# Circuit_version_4.net
KiCad netlist of a schematic drawn in Altium Designer
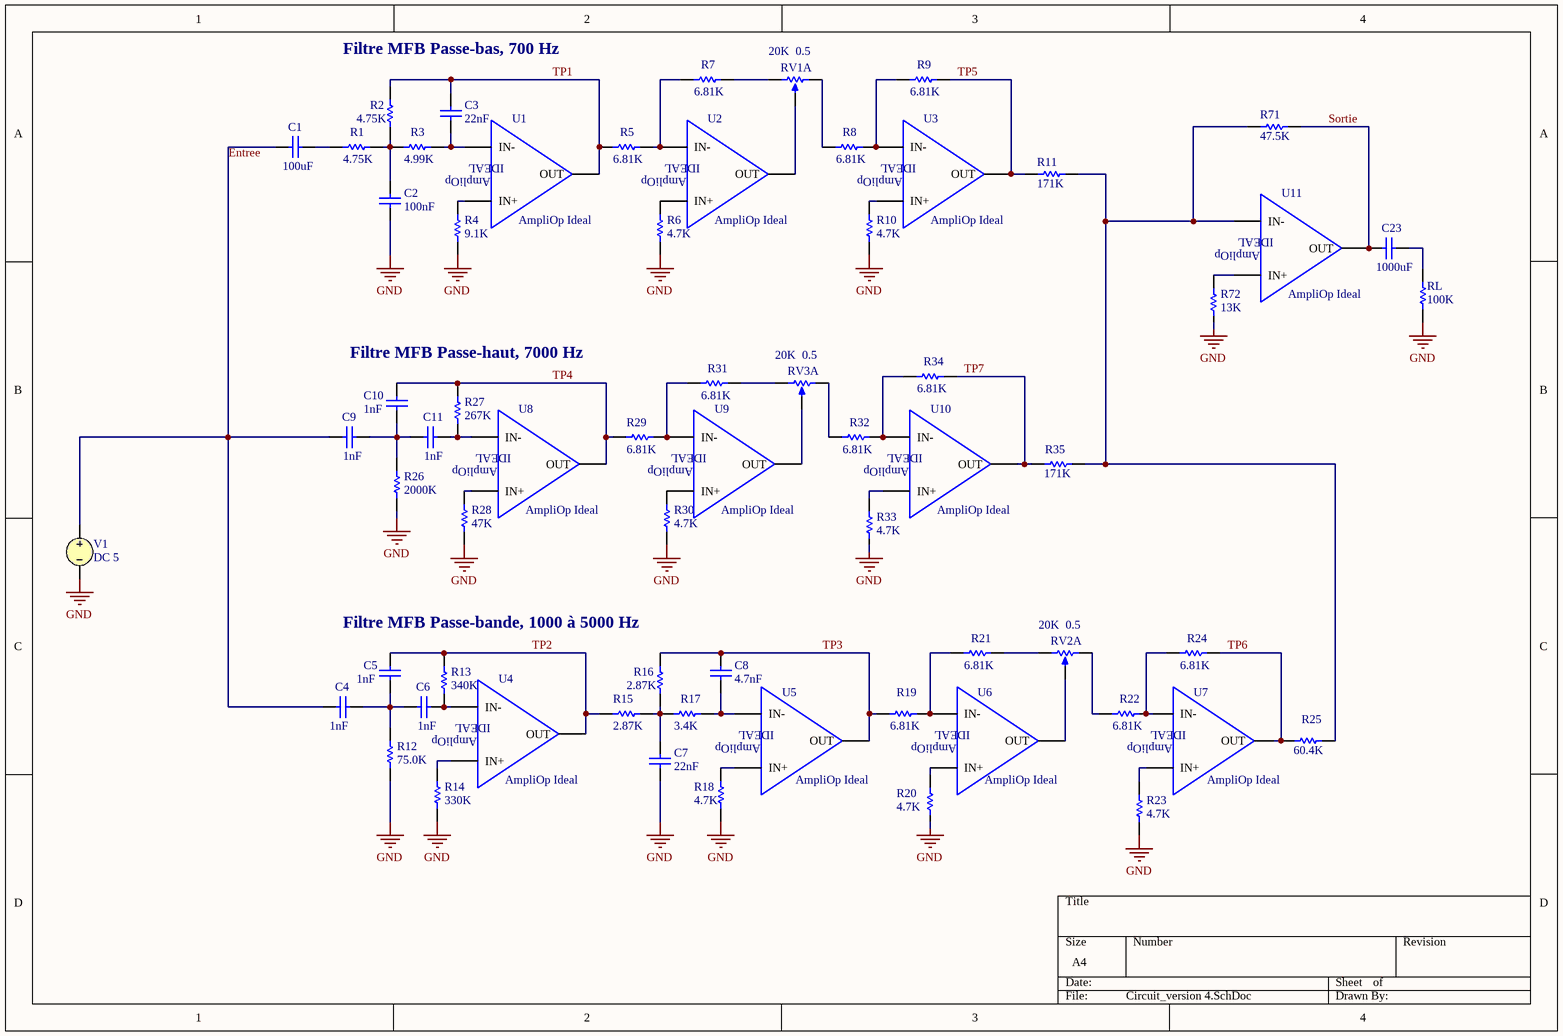
[diagram p0: Circuit_version 4.SchDoc]

(export (version "E")
  (design (tool "Eeschema 10.0.6"))
  (components
    (comp (ref "C1")
      (value "100uF")
      (footprint "RAD-0.3")
      (description "Capacitor")
      (fields (field (name "Comment") "Cap") (field (name "PUBLISHER") "Altium Limited"))
      (libsource (lib "Miscellaneous Devices") (part "Cap"))
    )
    (comp (ref "C2")
      (value "100nF")
      (footprint "RAD-0.3")
      (description "Capacitor")
      (fields (field (name "Comment") "Cap") (field (name "PUBLISHER") "Altium Limited"))
      (libsource (lib "Miscellaneous Devices") (part "Cap"))
    )
    (comp (ref "C3")
      (value "22nF")
      (footprint "RAD-0.3")
      (description "Capacitor")
      (fields (field (name "Comment") "Cap") (field (name "PUBLISHER") "Altium Limited"))
      (libsource (lib "Miscellaneous Devices") (part "Cap"))
    )
    (comp (ref "C4")
      (value "1nF")
      (footprint "RAD-0.3")
      (description "Capacitor")
      (fields (field (name "Comment") "Cap") (field (name "PUBLISHER") "Altium Limited"))
      (libsource (lib "Miscellaneous Devices") (part "Cap"))
    )
    (comp (ref "C5")
      (value "1nF")
      (footprint "RAD-0.3")
      (description "Capacitor")
      (fields (field (name "Comment") "Cap") (field (name "PUBLISHER") "Altium Limited"))
      (libsource (lib "Miscellaneous Devices") (part "Cap"))
    )
    (comp (ref "C6")
      (value "1nF")
      (footprint "RAD-0.3")
      (description "Capacitor")
      (fields (field (name "Comment") "Cap") (field (name "PUBLISHER") "Altium Limited"))
      (libsource (lib "Miscellaneous Devices") (part "Cap"))
    )
    (comp (ref "C7")
      (value "22nF")
      (footprint "RAD-0.3")
      (description "Capacitor")
      (fields (field (name "Comment") "Cap") (field (name "PUBLISHER") "Altium Limited"))
      (libsource (lib "Miscellaneous Devices") (part "Cap"))
    )
    (comp (ref "C8")
      (value "4.7nF")
      (footprint "RAD-0.3")
      (description "Capacitor")
      (fields (field (name "Comment") "Cap") (field (name "PUBLISHER") "Altium Limited"))
      (libsource (lib "Miscellaneous Devices") (part "Cap"))
    )
    (comp (ref "C9")
      (value "1nF")
      (footprint "RAD-0.3")
      (description "Capacitor")
      (fields (field (name "Comment") "Cap") (field (name "PUBLISHER") "Altium Limited"))
      (libsource (lib "Miscellaneous Devices") (part "Cap"))
    )
    (comp (ref "C10")
      (value "1nF")
      (footprint "RAD-0.3")
      (description "Capacitor")
      (fields (field (name "Comment") "Cap") (field (name "PUBLISHER") "Altium Limited"))
      (libsource (lib "Miscellaneous Devices") (part "Cap"))
    )
    (comp (ref "C11")
      (value "1nF")
      (footprint "RAD-0.3")
      (description "Capacitor")
      (fields (field (name "Comment") "Cap") (field (name "PUBLISHER") "Altium Limited"))
      (libsource (lib "Miscellaneous Devices") (part "Cap"))
    )
    (comp (ref "C23")
      (value "1000uF")
      (footprint "RAD-0.3")
      (description "Capacitor")
      (fields (field (name "Comment") "Cap") (field (name "PUBLISHER") "Altium Limited"))
      (libsource (lib "Miscellaneous Devices") (part "Cap"))
    )
    (comp (ref "R1")
      (value "4.75K")
      (footprint "AXIAL-0.3")
      (description "Resistor")
      (fields (field (name "Comment") "Res1") (field (name "PUBLISHER") "Altium Limited"))
      (libsource (lib "Miscellaneous Devices") (part "Res1"))
    )
    (comp (ref "R2")
      (value "4.75K")
      (footprint "AXIAL-0.3")
      (description "Resistor")
      (fields (field (name "Comment") "Res1") (field (name "PUBLISHER") "Altium Limited"))
      (libsource (lib "Miscellaneous Devices") (part "Res1"))
    )
    (comp (ref "R3")
      (value "4.99K")
      (footprint "AXIAL-0.3")
      (description "Resistor")
      (fields (field (name "Comment") "Res1") (field (name "PUBLISHER") "Altium Limited"))
      (libsource (lib "Miscellaneous Devices") (part "Res1"))
    )
    (comp (ref "R4")
      (value "9.1K")
      (footprint "AXIAL-0.3")
      (description "Resistor")
      (fields (field (name "Comment") "Res1") (field (name "PUBLISHER") "Altium Limited"))
      (libsource (lib "Miscellaneous Devices") (part "Res1"))
    )
    (comp (ref "R5")
      (value "6.81K")
      (footprint "AXIAL-0.3")
      (description "Resistor")
      (fields (field (name "Comment") "Res1") (field (name "PUBLISHER") "Altium Limited"))
      (libsource (lib "Miscellaneous Devices") (part "Res1"))
    )
    (comp (ref "R6")
      (value "4.7K")
      (footprint "AXIAL-0.3")
      (description "Resistor")
      (fields (field (name "Comment") "Res1") (field (name "PUBLISHER") "Altium Limited"))
      (libsource (lib "Miscellaneous Devices") (part "Res1"))
    )
    (comp (ref "R7")
      (value "6.81K")
      (footprint "AXIAL-0.3")
      (description "Resistor")
      (fields (field (name "Comment") "Res1") (field (name "PUBLISHER") "Altium Limited"))
      (libsource (lib "Miscellaneous Devices") (part "Res1"))
    )
    (comp (ref "R8")
      (value "6.81K")
      (footprint "AXIAL-0.3")
      (description "Resistor")
      (fields (field (name "Comment") "Res1") (field (name "PUBLISHER") "Altium Limited"))
      (libsource (lib "Miscellaneous Devices") (part "Res1"))
    )
    (comp (ref "R9")
      (value "6.81K")
      (footprint "AXIAL-0.3")
      (description "Resistor")
      (fields (field (name "Comment") "Res1") (field (name "PUBLISHER") "Altium Limited"))
      (libsource (lib "Miscellaneous Devices") (part "Res1"))
    )
    (comp (ref "R10")
      (value "4.7K")
      (footprint "AXIAL-0.3")
      (description "Resistor")
      (fields (field (name "Comment") "Res1") (field (name "PUBLISHER") "Altium Limited"))
      (libsource (lib "Miscellaneous Devices") (part "Res1"))
    )
    (comp (ref "R11")
      (value "171K")
      (footprint "AXIAL-0.3")
      (description "Resistor")
      (fields (field (name "Comment") "Res1") (field (name "PUBLISHER") "Altium Limited"))
      (libsource (lib "Miscellaneous Devices") (part "Res1"))
    )
    (comp (ref "R12")
      (value "75.0K")
      (footprint "AXIAL-0.3")
      (description "Resistor")
      (fields (field (name "Comment") "Res1") (field (name "PUBLISHER") "Altium Limited"))
      (libsource (lib "Miscellaneous Devices") (part "Res1"))
    )
    (comp (ref "R13")
      (value "340K")
      (footprint "AXIAL-0.3")
      (description "Resistor")
      (fields (field (name "Comment") "Res1") (field (name "PUBLISHER") "Altium Limited"))
      (libsource (lib "Miscellaneous Devices") (part "Res1"))
    )
    (comp (ref "R14")
      (value "330K")
      (footprint "AXIAL-0.3")
      (description "Resistor")
      (fields (field (name "Comment") "Res1") (field (name "PUBLISHER") "Altium Limited"))
      (libsource (lib "Miscellaneous Devices") (part "Res1"))
    )
    (comp (ref "R15")
      (value "2.87K")
      (footprint "AXIAL-0.3")
      (description "Resistor")
      (fields (field (name "Comment") "Res1") (field (name "PUBLISHER") "Altium Limited"))
      (libsource (lib "Miscellaneous Devices") (part "Res1"))
    )
    (comp (ref "R16")
      (value "2.87K")
      (footprint "AXIAL-0.3")
      (description "Resistor")
      (fields (field (name "Comment") "Res1") (field (name "PUBLISHER") "Altium Limited"))
      (libsource (lib "Miscellaneous Devices") (part "Res1"))
    )
    (comp (ref "R17")
      (value "3.4K")
      (footprint "AXIAL-0.3")
      (description "Resistor")
      (fields (field (name "Comment") "Res1") (field (name "PUBLISHER") "Altium Limited"))
      (libsource (lib "Miscellaneous Devices") (part "Res1"))
    )
    (comp (ref "R18")
      (value "4.7K")
      (footprint "AXIAL-0.3")
      (description "Resistor")
      (fields (field (name "Comment") "Res1") (field (name "PUBLISHER") "Altium Limited"))
      (libsource (lib "Miscellaneous Devices") (part "Res1"))
    )
    (comp (ref "R19")
      (value "6.81K")
      (footprint "AXIAL-0.3")
      (description "Resistor")
      (fields (field (name "Comment") "Res1") (field (name "PUBLISHER") "Altium Limited"))
      (libsource (lib "Miscellaneous Devices") (part "Res1"))
    )
    (comp (ref "R20")
      (value "4.7K")
      (footprint "AXIAL-0.3")
      (description "Resistor")
      (fields (field (name "Comment") "Res1") (field (name "PUBLISHER") "Altium Limited"))
      (libsource (lib "Miscellaneous Devices") (part "Res1"))
    )
    (comp (ref "R21")
      (value "6.81K")
      (footprint "AXIAL-0.3")
      (description "Resistor")
      (fields (field (name "Comment") "Res1") (field (name "PUBLISHER") "Altium Limited"))
      (libsource (lib "Miscellaneous Devices") (part "Res1"))
    )
    (comp (ref "R22")
      (value "6.81K")
      (footprint "AXIAL-0.3")
      (description "Resistor")
      (fields (field (name "Comment") "Res1") (field (name "PUBLISHER") "Altium Limited"))
      (libsource (lib "Miscellaneous Devices") (part "Res1"))
    )
    (comp (ref "R23")
      (value "4.7K")
      (footprint "AXIAL-0.3")
      (description "Resistor")
      (fields (field (name "Comment") "Res1") (field (name "PUBLISHER") "Altium Limited"))
      (libsource (lib "Miscellaneous Devices") (part "Res1"))
    )
    (comp (ref "R24")
      (value "6.81K")
      (footprint "AXIAL-0.3")
      (description "Resistor")
      (fields (field (name "Comment") "Res1") (field (name "PUBLISHER") "Altium Limited"))
      (libsource (lib "Miscellaneous Devices") (part "Res1"))
    )
    (comp (ref "R25")
      (value "60.4K")
      (footprint "AXIAL-0.3")
      (description "Resistor")
      (fields (field (name "Comment") "Res1") (field (name "PUBLISHER") "Altium Limited"))
      (libsource (lib "Miscellaneous Devices") (part "Res1"))
    )
    (comp (ref "R26")
      (value "2000K")
      (footprint "AXIAL-0.3")
      (description "Resistor")
      (fields (field (name "Comment") "Res1") (field (name "PUBLISHER") "Altium Limited"))
      (libsource (lib "Miscellaneous Devices") (part "Res1"))
    )
    (comp (ref "R27")
      (value "267K")
      (footprint "AXIAL-0.3")
      (description "Resistor")
      (fields (field (name "Comment") "Res1") (field (name "PUBLISHER") "Altium Limited"))
      (libsource (lib "Miscellaneous Devices") (part "Res1"))
    )
    (comp (ref "R28")
      (value "47K")
      (footprint "AXIAL-0.3")
      (description "Resistor")
      (fields (field (name "Comment") "Res1") (field (name "PUBLISHER") "Altium Limited"))
      (libsource (lib "Miscellaneous Devices") (part "Res1"))
    )
    (comp (ref "R29")
      (value "6.81K")
      (footprint "AXIAL-0.3")
      (description "Resistor")
      (fields (field (name "Comment") "Res1") (field (name "PUBLISHER") "Altium Limited"))
      (libsource (lib "Miscellaneous Devices") (part "Res1"))
    )
    (comp (ref "R30")
      (value "4.7K")
      (footprint "AXIAL-0.3")
      (description "Resistor")
      (fields (field (name "Comment") "Res1") (field (name "PUBLISHER") "Altium Limited"))
      (libsource (lib "Miscellaneous Devices") (part "Res1"))
    )
    (comp (ref "R31")
      (value "6.81K")
      (footprint "AXIAL-0.3")
      (description "Resistor")
      (fields (field (name "Comment") "Res1") (field (name "PUBLISHER") "Altium Limited"))
      (libsource (lib "Miscellaneous Devices") (part "Res1"))
    )
    (comp (ref "R32")
      (value "6.81K")
      (footprint "AXIAL-0.3")
      (description "Resistor")
      (fields (field (name "Comment") "Res1") (field (name "PUBLISHER") "Altium Limited"))
      (libsource (lib "Miscellaneous Devices") (part "Res1"))
    )
    (comp (ref "R33")
      (value "4.7K")
      (footprint "AXIAL-0.3")
      (description "Resistor")
      (fields (field (name "Comment") "Res1") (field (name "PUBLISHER") "Altium Limited"))
      (libsource (lib "Miscellaneous Devices") (part "Res1"))
    )
    (comp (ref "R34")
      (value "6.81K")
      (footprint "AXIAL-0.3")
      (description "Resistor")
      (fields (field (name "Comment") "Res1") (field (name "PUBLISHER") "Altium Limited"))
      (libsource (lib "Miscellaneous Devices") (part "Res1"))
    )
    (comp (ref "R35")
      (value "171K")
      (footprint "AXIAL-0.3")
      (description "Resistor")
      (fields (field (name "Comment") "Res1") (field (name "PUBLISHER") "Altium Limited"))
      (libsource (lib "Miscellaneous Devices") (part "Res1"))
    )
    (comp (ref "R71")
      (value "47.5K")
      (footprint "AXIAL-0.3")
      (description "Resistor")
      (fields (field (name "Comment") "Res1") (field (name "PUBLISHER") "Altium Limited"))
      (libsource (lib "Miscellaneous Devices") (part "Res1"))
    )
    (comp (ref "R72")
      (value "13K")
      (footprint "AXIAL-0.3")
      (description "Resistor")
      (fields (field (name "Comment") "Res1") (field (name "PUBLISHER") "Altium Limited"))
      (libsource (lib "Miscellaneous Devices") (part "Res1"))
    )
    (comp (ref "RL")
      (value "100K")
      (footprint "AXIAL-0.3")
      (description "Resistor")
      (fields (field (name "Comment") "Res1") (field (name "PUBLISHER") "Altium Limited"))
      (libsource (lib "Miscellaneous Devices") (part "Res1"))
    )
    (comp (ref "RV1A")
      (value "20K")
      (footprint "VR5")
      (description "Potentiometer")
      (fields
        (field (name "SET POSITION") "0.5")
        (field (name "Comment") "RPot")
        (field (name "PUBLISHER") "Altium Limited")
      )
      (libsource (lib "Miscellaneous Devices") (part "RPot"))
    )
    (comp (ref "RV2A")
      (value "20K")
      (footprint "VR5")
      (description "Potentiometer")
      (fields
        (field (name "SET POSITION") "0.5")
        (field (name "Comment") "RPot")
        (field (name "PUBLISHER") "Altium Limited")
      )
      (libsource (lib "Miscellaneous Devices") (part "RPot"))
    )
    (comp (ref "RV3A")
      (value "20K")
      (footprint "VR5")
      (description "Potentiometer")
      (fields
        (field (name "SET POSITION") "0.5")
        (field (name "Comment") "RPot")
        (field (name "PUBLISHER") "Altium Limited")
      )
      (libsource (lib "Miscellaneous Devices") (part "RPot"))
    )
    (comp (ref "U1") (value "AmpliOp Ideal") (libsource (lib "Librarie_S2") (part "AmpliOp_ideal")))
    (comp (ref "U2") (value "AmpliOp Ideal") (libsource (lib "Librarie_S2") (part "AmpliOp_ideal")))
    (comp (ref "U3") (value "AmpliOp Ideal") (libsource (lib "Librarie_S2") (part "AmpliOp_ideal")))
    (comp (ref "U4") (value "AmpliOp Ideal") (libsource (lib "Librarie_S2") (part "AmpliOp_ideal")))
    (comp (ref "U5") (value "AmpliOp Ideal") (libsource (lib "Librarie_S2") (part "AmpliOp_ideal")))
    (comp (ref "U6") (value "AmpliOp Ideal") (libsource (lib "Librarie_S2") (part "AmpliOp_ideal")))
    (comp (ref "U7") (value "AmpliOp Ideal") (libsource (lib "Librarie_S2") (part "AmpliOp_ideal")))
    (comp (ref "U8") (value "AmpliOp Ideal") (libsource (lib "Librarie_S2") (part "AmpliOp_ideal")))
    (comp (ref "U9") (value "AmpliOp Ideal") (libsource (lib "Librarie_S2") (part "AmpliOp_ideal")))
    (comp (ref "U10") (value "AmpliOp Ideal") (libsource (lib "Librarie_S2") (part "AmpliOp_ideal")))
    (comp (ref "U11") (value "AmpliOp Ideal") (libsource (lib "Librarie_S2") (part "AmpliOp_ideal")))
    (comp (ref "V1")
      (value "DC 5")
      (description "Voltage Source")
      (fields (field (name "PUBLISHER") "Altium Limited"))
      (libsource (lib "Simulation Generic Components") (part "VSRC"))
    )
  )
  (nets
    (net (code "1") (name "/Entree") (class "Default")
      (node (ref "C1") (pin "1") (pinfunction "1_1") (pintype "passive"))
      (node (ref "C4") (pin "1") (pinfunction "1_1") (pintype "passive"))
      (node (ref "C9") (pin "1") (pinfunction "1_1") (pintype "passive"))
      (node (ref "V1") (pin "1") (pinfunction "1_1") (pintype "passive"))
    )
    (net (code "2") (name "/Sortie") (class "Default")
      (node (ref "C23") (pin "1") (pinfunction "1_1") (pintype "passive"))
      (node (ref "R71") (pin "2") (pinfunction "2_2") (pintype "passive"))
      (node (ref "U11") (pin "3") (pinfunction "OUT_3") (pintype "passive"))
    )
    (net (code "3") (name "/TP1") (class "Default")
      (node (ref "C3") (pin "1") (pinfunction "1_1") (pintype "passive"))
      (node (ref "R2") (pin "1") (pinfunction "1_1") (pintype "passive"))
      (node (ref "R5") (pin "1") (pinfunction "1_1") (pintype "passive"))
      (node (ref "U1") (pin "3") (pinfunction "OUT_3") (pintype "passive"))
    )
    (net (code "4") (name "/TP2") (class "Default")
      (node (ref "C5") (pin "1") (pinfunction "1_1") (pintype "passive"))
      (node (ref "R13") (pin "1") (pinfunction "1_1") (pintype "passive"))
      (node (ref "R15") (pin "1") (pinfunction "1_1") (pintype "passive"))
      (node (ref "U4") (pin "3") (pinfunction "OUT_3") (pintype "passive"))
    )
    (net (code "5") (name "/TP3") (class "Default")
      (node (ref "C8") (pin "1") (pinfunction "1_1") (pintype "passive"))
      (node (ref "R16") (pin "1") (pinfunction "1_1") (pintype "passive"))
      (node (ref "R19") (pin "1") (pinfunction "1_1") (pintype "passive"))
      (node (ref "U5") (pin "3") (pinfunction "OUT_3") (pintype "passive"))
    )
    (net (code "6") (name "/TP4") (class "Default")
      (node (ref "C10") (pin "1") (pinfunction "1_1") (pintype "passive"))
      (node (ref "R27") (pin "1") (pinfunction "1_1") (pintype "passive"))
      (node (ref "R29") (pin "1") (pinfunction "1_1") (pintype "passive"))
      (node (ref "U8") (pin "3") (pinfunction "OUT_3") (pintype "passive"))
    )
    (net (code "7") (name "/TP5") (class "Default")
      (node (ref "R11") (pin "1") (pinfunction "1_1") (pintype "passive"))
      (node (ref "R9") (pin "2") (pinfunction "2_2") (pintype "passive"))
      (node (ref "U3") (pin "3") (pinfunction "OUT_3") (pintype "passive"))
    )
    (net (code "8") (name "/TP6") (class "Default")
      (node (ref "R24") (pin "2") (pinfunction "2_2") (pintype "passive"))
      (node (ref "R25") (pin "1") (pinfunction "1_1") (pintype "passive"))
      (node (ref "U7") (pin "3") (pinfunction "OUT_3") (pintype "passive"))
    )
    (net (code "9") (name "/TP7") (class "Default")
      (node (ref "R34") (pin "2") (pinfunction "2_2") (pintype "passive"))
      (node (ref "R35") (pin "1") (pinfunction "1_1") (pintype "passive"))
      (node (ref "U10") (pin "3") (pinfunction "OUT_3") (pintype "passive"))
    )
    (net (code "10") (name "GND") (class "Default")
      (node (ref "C2") (pin "2") (pinfunction "2_2") (pintype "passive"))
      (node (ref "C7") (pin "2") (pinfunction "2_2") (pintype "passive"))
      (node (ref "R10") (pin "2") (pinfunction "2_2") (pintype "passive"))
      (node (ref "R12") (pin "2") (pinfunction "2_2") (pintype "passive"))
      (node (ref "R14") (pin "2") (pinfunction "2_2") (pintype "passive"))
      (node (ref "R18") (pin "2") (pinfunction "2_2") (pintype "passive"))
      (node (ref "R20") (pin "2") (pinfunction "2_2") (pintype "passive"))
      (node (ref "R23") (pin "2") (pinfunction "2_2") (pintype "passive"))
      (node (ref "R26") (pin "2") (pinfunction "2_2") (pintype "passive"))
      (node (ref "R28") (pin "2") (pinfunction "2_2") (pintype "passive"))
      (node (ref "R30") (pin "2") (pinfunction "2_2") (pintype "passive"))
      (node (ref "R33") (pin "2") (pinfunction "2_2") (pintype "passive"))
      (node (ref "R4") (pin "2") (pinfunction "2_2") (pintype "passive"))
      (node (ref "R6") (pin "2") (pinfunction "2_2") (pintype "passive"))
      (node (ref "R72") (pin "2") (pinfunction "2_2") (pintype "passive"))
      (node (ref "RL") (pin "1") (pinfunction "1_1") (pintype "passive"))
      (node (ref "V1") (pin "2") (pinfunction "2_2") (pintype "passive"))
    )
    (net (code "11") (name "Net-(C1-Pad2)") (class "Default")
      (node (ref "C1") (pin "2") (pinfunction "2_2") (pintype "passive"))
      (node (ref "R1") (pin "1") (pinfunction "1_1") (pintype "passive"))
    )
    (net (code "12") (name "Net-(C2-Pad1)") (class "Default")
      (node (ref "C2") (pin "1") (pinfunction "1_1") (pintype "passive"))
      (node (ref "R1") (pin "2") (pinfunction "2_2") (pintype "passive"))
      (node (ref "R2") (pin "2") (pinfunction "2_2") (pintype "passive"))
      (node (ref "R3") (pin "1") (pinfunction "1_1") (pintype "passive"))
    )
    (net (code "13") (name "Net-(C4-Pad2)") (class "Default")
      (node (ref "C4") (pin "2") (pinfunction "2_2") (pintype "passive"))
      (node (ref "C5") (pin "2") (pinfunction "2_2") (pintype "passive"))
      (node (ref "C6") (pin "1") (pinfunction "1_1") (pintype "passive"))
      (node (ref "R12") (pin "1") (pinfunction "1_1") (pintype "passive"))
    )
    (net (code "14") (name "Net-(C7-Pad1)") (class "Default")
      (node (ref "C7") (pin "1") (pinfunction "1_1") (pintype "passive"))
      (node (ref "R15") (pin "2") (pinfunction "2_2") (pintype "passive"))
      (node (ref "R16") (pin "2") (pinfunction "2_2") (pintype "passive"))
      (node (ref "R17") (pin "1") (pinfunction "1_1") (pintype "passive"))
    )
    (net (code "15") (name "Net-(C10-Pad2)") (class "Default")
      (node (ref "C10") (pin "2") (pinfunction "2_2") (pintype "passive"))
      (node (ref "C11") (pin "1") (pinfunction "1_1") (pintype "passive"))
      (node (ref "C9") (pin "2") (pinfunction "2_2") (pintype "passive"))
      (node (ref "R26") (pin "1") (pinfunction "1_1") (pintype "passive"))
    )
    (net (code "16") (name "Net-(C23-Pad2)") (class "Default")
      (node (ref "C23") (pin "2") (pinfunction "2_2") (pintype "passive"))
      (node (ref "RL") (pin "2") (pinfunction "2_2") (pintype "passive"))
    )
    (net (code "17") (name "Net-(RV1A-BOT)") (class "Default")
      (node (ref "R8") (pin "1") (pinfunction "1_1") (pintype "passive"))
      (node (ref "RV1A") (pin "2") (pinfunction "BOT_2") (pintype "passive"))
    )
    (net (code "18") (name "Net-(RV1A-TAP)") (class "Default")
      (node (ref "RV1A") (pin "3") (pinfunction "TAP_3") (pintype "passive"))
      (node (ref "U2") (pin "3") (pinfunction "OUT_3") (pintype "passive"))
    )
    (net (code "19") (name "Net-(RV1A-TOP)") (class "Default")
      (node (ref "R7") (pin "2") (pinfunction "2_2") (pintype "passive"))
      (node (ref "RV1A") (pin "1") (pinfunction "TOP_1") (pintype "passive"))
    )
    (net (code "20") (name "Net-(RV2A-BOT)") (class "Default")
      (node (ref "R22") (pin "1") (pinfunction "1_1") (pintype "passive"))
      (node (ref "RV2A") (pin "2") (pinfunction "BOT_2") (pintype "passive"))
    )
    (net (code "21") (name "Net-(RV2A-TAP)") (class "Default")
      (node (ref "RV2A") (pin "3") (pinfunction "TAP_3") (pintype "passive"))
      (node (ref "U6") (pin "3") (pinfunction "OUT_3") (pintype "passive"))
    )
    (net (code "22") (name "Net-(RV2A-TOP)") (class "Default")
      (node (ref "R21") (pin "2") (pinfunction "2_2") (pintype "passive"))
      (node (ref "RV2A") (pin "1") (pinfunction "TOP_1") (pintype "passive"))
    )
    (net (code "23") (name "Net-(RV3A-BOT)") (class "Default")
      (node (ref "R32") (pin "1") (pinfunction "1_1") (pintype "passive"))
      (node (ref "RV3A") (pin "2") (pinfunction "BOT_2") (pintype "passive"))
    )
    (net (code "24") (name "Net-(RV3A-TAP)") (class "Default")
      (node (ref "RV3A") (pin "3") (pinfunction "TAP_3") (pintype "passive"))
      (node (ref "U9") (pin "3") (pinfunction "OUT_3") (pintype "passive"))
    )
    (net (code "25") (name "Net-(RV3A-TOP)") (class "Default")
      (node (ref "R31") (pin "2") (pinfunction "2_2") (pintype "passive"))
      (node (ref "RV3A") (pin "1") (pinfunction "TOP_1") (pintype "passive"))
    )
    (net (code "26") (name "Net-(U1-IN+)") (class "Default")
      (node (ref "R4") (pin "1") (pinfunction "1_1") (pintype "passive"))
      (node (ref "U1") (pin "1") (pinfunction "IN+_1") (pintype "passive"))
    )
    (net (code "27") (name "Net-(U1-IN-)") (class "Default")
      (node (ref "C3") (pin "2") (pinfunction "2_2") (pintype "passive"))
      (node (ref "R3") (pin "2") (pinfunction "2_2") (pintype "passive"))
      (node (ref "U1") (pin "2") (pinfunction "IN-_2") (pintype "passive"))
    )
    (net (code "28") (name "Net-(U2-IN+)") (class "Default")
      (node (ref "R6") (pin "1") (pinfunction "1_1") (pintype "passive"))
      (node (ref "U2") (pin "1") (pinfunction "IN+_1") (pintype "passive"))
    )
    (net (code "29") (name "Net-(U2-IN-)") (class "Default")
      (node (ref "R5") (pin "2") (pinfunction "2_2") (pintype "passive"))
      (node (ref "R7") (pin "1") (pinfunction "1_1") (pintype "passive"))
      (node (ref "U2") (pin "2") (pinfunction "IN-_2") (pintype "passive"))
    )
    (net (code "30") (name "Net-(U3-IN+)") (class "Default")
      (node (ref "R10") (pin "1") (pinfunction "1_1") (pintype "passive"))
      (node (ref "U3") (pin "1") (pinfunction "IN+_1") (pintype "passive"))
    )
    (net (code "31") (name "Net-(U3-IN-)") (class "Default")
      (node (ref "R8") (pin "2") (pinfunction "2_2") (pintype "passive"))
      (node (ref "R9") (pin "1") (pinfunction "1_1") (pintype "passive"))
      (node (ref "U3") (pin "2") (pinfunction "IN-_2") (pintype "passive"))
    )
    (net (code "32") (name "Net-(U4-IN+)") (class "Default")
      (node (ref "R14") (pin "1") (pinfunction "1_1") (pintype "passive"))
      (node (ref "U4") (pin "1") (pinfunction "IN+_1") (pintype "passive"))
    )
    (net (code "33") (name "Net-(U4-IN-)") (class "Default")
      (node (ref "C6") (pin "2") (pinfunction "2_2") (pintype "passive"))
      (node (ref "R13") (pin "2") (pinfunction "2_2") (pintype "passive"))
      (node (ref "U4") (pin "2") (pinfunction "IN-_2") (pintype "passive"))
    )
    (net (code "34") (name "Net-(U5-IN+)") (class "Default")
      (node (ref "R18") (pin "1") (pinfunction "1_1") (pintype "passive"))
      (node (ref "U5") (pin "1") (pinfunction "IN+_1") (pintype "passive"))
    )
    (net (code "35") (name "Net-(U5-IN-)") (class "Default")
      (node (ref "C8") (pin "2") (pinfunction "2_2") (pintype "passive"))
      (node (ref "R17") (pin "2") (pinfunction "2_2") (pintype "passive"))
      (node (ref "U5") (pin "2") (pinfunction "IN-_2") (pintype "passive"))
    )
    (net (code "36") (name "Net-(U6-IN+)") (class "Default")
      (node (ref "R20") (pin "1") (pinfunction "1_1") (pintype "passive"))
      (node (ref "U6") (pin "1") (pinfunction "IN+_1") (pintype "passive"))
    )
    (net (code "37") (name "Net-(U6-IN-)") (class "Default")
      (node (ref "R19") (pin "2") (pinfunction "2_2") (pintype "passive"))
      (node (ref "R21") (pin "1") (pinfunction "1_1") (pintype "passive"))
      (node (ref "U6") (pin "2") (pinfunction "IN-_2") (pintype "passive"))
    )
    (net (code "38") (name "Net-(U7-IN+)") (class "Default")
      (node (ref "R23") (pin "1") (pinfunction "1_1") (pintype "passive"))
      (node (ref "U7") (pin "1") (pinfunction "IN+_1") (pintype "passive"))
    )
    (net (code "39") (name "Net-(U7-IN-)") (class "Default")
      (node (ref "R22") (pin "2") (pinfunction "2_2") (pintype "passive"))
      (node (ref "R24") (pin "1") (pinfunction "1_1") (pintype "passive"))
      (node (ref "U7") (pin "2") (pinfunction "IN-_2") (pintype "passive"))
    )
    (net (code "40") (name "Net-(U8-IN+)") (class "Default")
      (node (ref "R28") (pin "1") (pinfunction "1_1") (pintype "passive"))
      (node (ref "U8") (pin "1") (pinfunction "IN+_1") (pintype "passive"))
    )
    (net (code "41") (name "Net-(U8-IN-)") (class "Default")
      (node (ref "C11") (pin "2") (pinfunction "2_2") (pintype "passive"))
      (node (ref "R27") (pin "2") (pinfunction "2_2") (pintype "passive"))
      (node (ref "U8") (pin "2") (pinfunction "IN-_2") (pintype "passive"))
    )
    (net (code "42") (name "Net-(U9-IN+)") (class "Default")
      (node (ref "R30") (pin "1") (pinfunction "1_1") (pintype "passive"))
      (node (ref "U9") (pin "1") (pinfunction "IN+_1") (pintype "passive"))
    )
    (net (code "43") (name "Net-(U9-IN-)") (class "Default")
      (node (ref "R29") (pin "2") (pinfunction "2_2") (pintype "passive"))
      (node (ref "R31") (pin "1") (pinfunction "1_1") (pintype "passive"))
      (node (ref "U9") (pin "2") (pinfunction "IN-_2") (pintype "passive"))
    )
    (net (code "44") (name "Net-(U10-IN+)") (class "Default")
      (node (ref "R33") (pin "1") (pinfunction "1_1") (pintype "passive"))
      (node (ref "U10") (pin "1") (pinfunction "IN+_1") (pintype "passive"))
    )
    (net (code "45") (name "Net-(U10-IN-)") (class "Default")
      (node (ref "R32") (pin "2") (pinfunction "2_2") (pintype "passive"))
      (node (ref "R34") (pin "1") (pinfunction "1_1") (pintype "passive"))
      (node (ref "U10") (pin "2") (pinfunction "IN-_2") (pintype "passive"))
    )
    (net (code "46") (name "Net-(U11-IN+)") (class "Default")
      (node (ref "R72") (pin "1") (pinfunction "1_1") (pintype "passive"))
      (node (ref "U11") (pin "1") (pinfunction "IN+_1") (pintype "passive"))
    )
    (net (code "47") (name "Net-(U11-IN-)") (class "Default")
      (node (ref "R11") (pin "2") (pinfunction "2_2") (pintype "passive"))
      (node (ref "R25") (pin "2") (pinfunction "2_2") (pintype "passive"))
      (node (ref "R35") (pin "2") (pinfunction "2_2") (pintype "passive"))
      (node (ref "R71") (pin "1") (pinfunction "1_1") (pintype "passive"))
      (node (ref "U11") (pin "2") (pinfunction "IN-_2") (pintype "passive"))
    )
  )
)
